# W602X.net
KiCad netlist of a schematic drawn in EAGLE
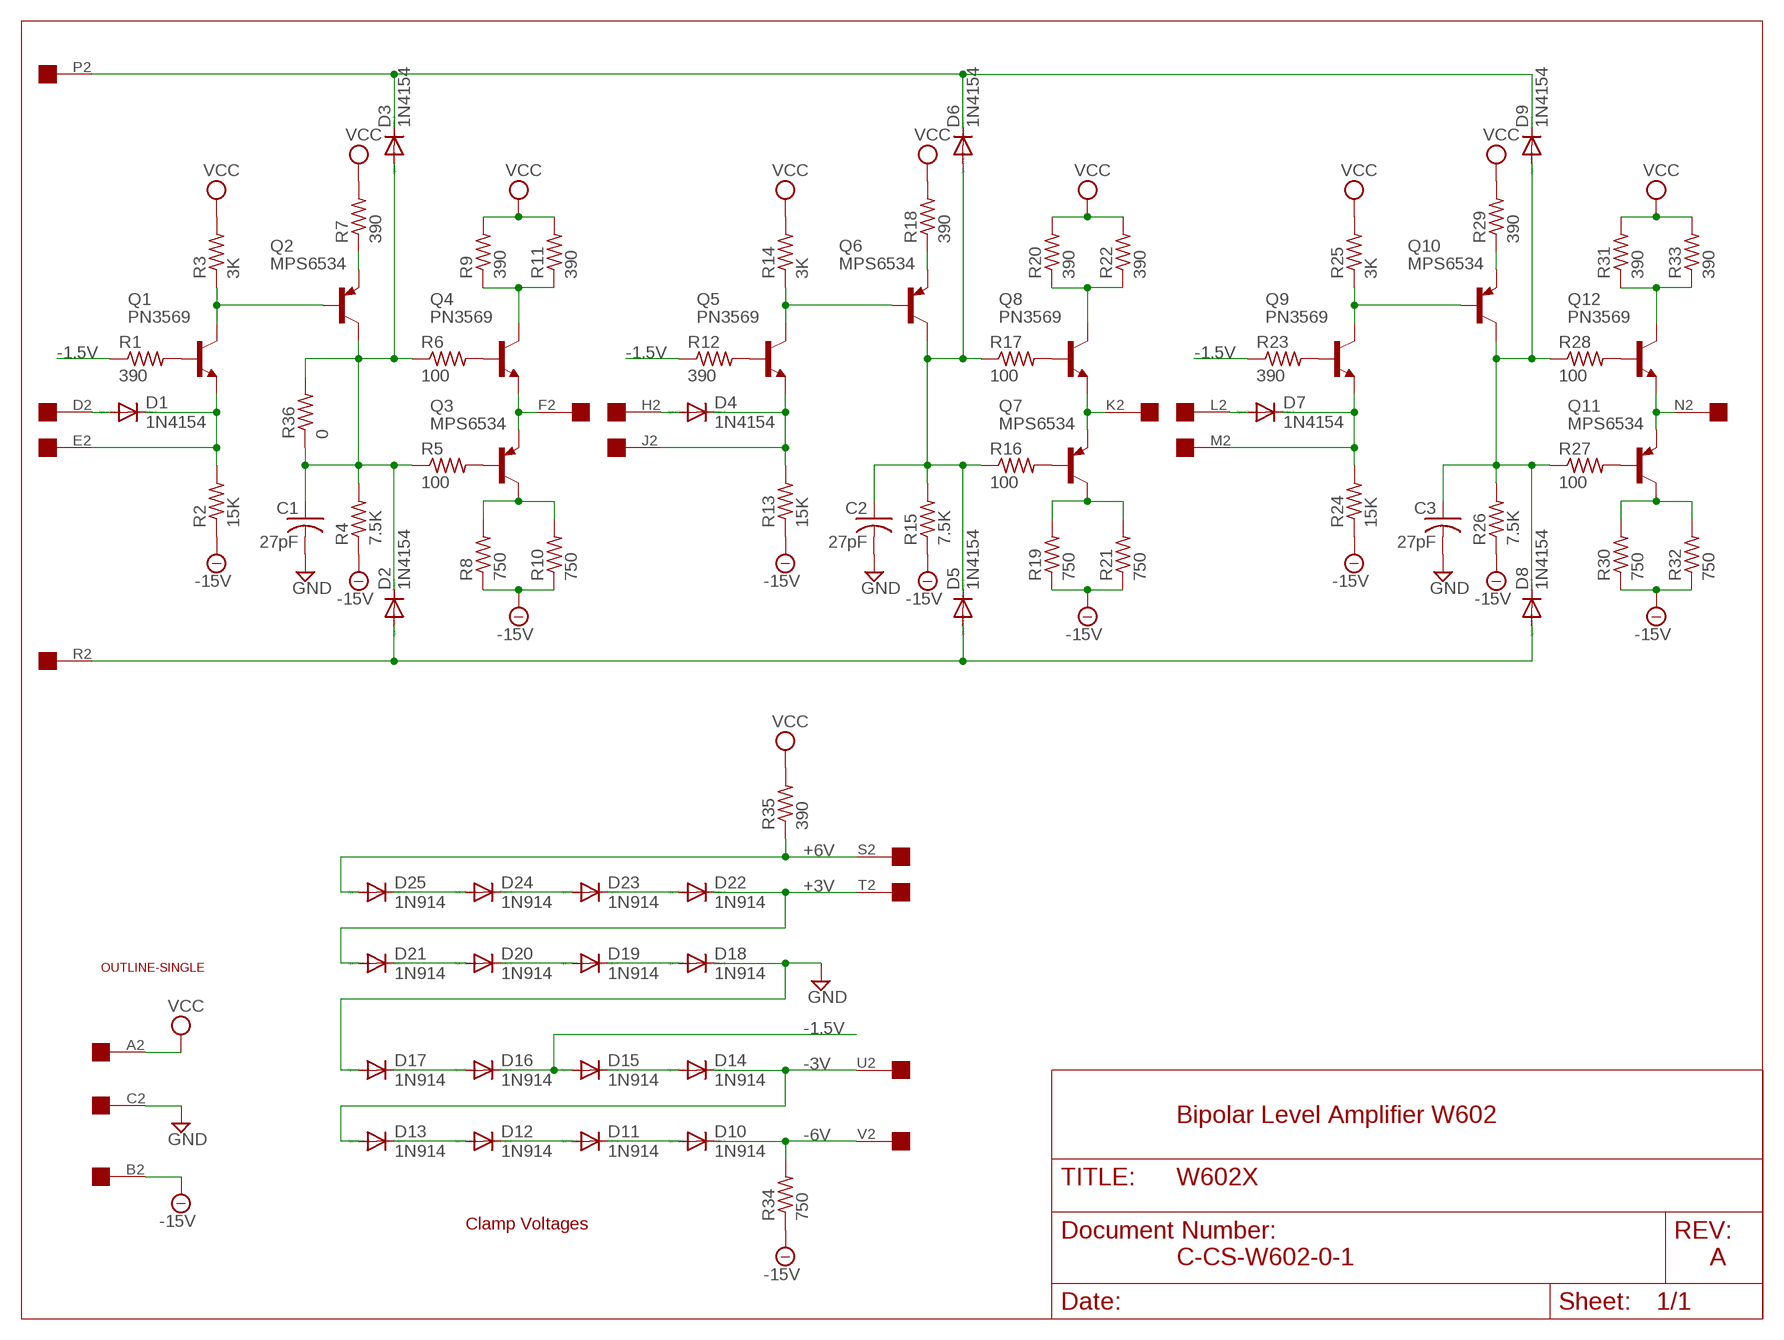
[diagram p0: schematic, sheet 1]

(export (version "E")
  (design (tool "Eeschema 10.0.6"))
  (components
    (comp (ref "C1")
      (value "27pF")
      (footprint "eagle-import:C063-025X075")
      (libsource (lib "eagle-import") (part "C-US"))
    )
    (comp (ref "C2")
      (value "27pF")
      (footprint "eagle-import:C063-025X075")
      (libsource (lib "eagle-import") (part "C-US"))
    )
    (comp (ref "C3")
      (value "27pF")
      (footprint "eagle-import:C063-025X075")
      (libsource (lib "eagle-import") (part "C-US"))
    )
    (comp (ref "D1")
      (value "1N4154")
      (footprint "eagle-import:DO35-10")
      (libsource (lib "eagle-import") (part "DIODE-DO35-10"))
    )
    (comp (ref "D2")
      (value "1N4154")
      (footprint "eagle-import:DO35-10")
      (libsource (lib "eagle-import") (part "DIODE-DO35-10"))
    )
    (comp (ref "D3")
      (value "1N4154")
      (footprint "eagle-import:DO35-10")
      (libsource (lib "eagle-import") (part "DIODE-DO35-10"))
    )
    (comp (ref "D4")
      (value "1N4154")
      (footprint "eagle-import:DO35-10")
      (libsource (lib "eagle-import") (part "DIODE-DO35-10"))
    )
    (comp (ref "D5")
      (value "1N4154")
      (footprint "eagle-import:DO35-10")
      (libsource (lib "eagle-import") (part "DIODE-DO35-10"))
    )
    (comp (ref "D6")
      (value "1N4154")
      (footprint "eagle-import:DO35-10")
      (libsource (lib "eagle-import") (part "DIODE-DO35-10"))
    )
    (comp (ref "D7")
      (value "1N4154")
      (footprint "eagle-import:DO35-10")
      (libsource (lib "eagle-import") (part "DIODE-DO35-10"))
    )
    (comp (ref "D8")
      (value "1N4154")
      (footprint "eagle-import:DO35-10")
      (libsource (lib "eagle-import") (part "DIODE-DO35-10"))
    )
    (comp (ref "D9")
      (value "1N4154")
      (footprint "eagle-import:DO35-10")
      (libsource (lib "eagle-import") (part "DIODE-DO35-10"))
    )
    (comp (ref "D10")
      (value "1N914")
      (footprint "eagle-import:DO35-10")
      (libsource (lib "eagle-import") (part "DIODE-DO35-10"))
    )
    (comp (ref "D11")
      (value "1N914")
      (footprint "eagle-import:DO35-10")
      (libsource (lib "eagle-import") (part "DIODE-DO35-10"))
    )
    (comp (ref "D12")
      (value "1N914")
      (footprint "eagle-import:DO35-10")
      (libsource (lib "eagle-import") (part "DIODE-DO35-10"))
    )
    (comp (ref "D13")
      (value "1N914")
      (footprint "eagle-import:DO35-10")
      (libsource (lib "eagle-import") (part "DIODE-DO35-10"))
    )
    (comp (ref "D14")
      (value "1N914")
      (footprint "eagle-import:DO35-10")
      (libsource (lib "eagle-import") (part "DIODE-DO35-10"))
    )
    (comp (ref "D15")
      (value "1N914")
      (footprint "eagle-import:DO35-10")
      (libsource (lib "eagle-import") (part "DIODE-DO35-10"))
    )
    (comp (ref "D16")
      (value "1N914")
      (footprint "eagle-import:DO35-10")
      (libsource (lib "eagle-import") (part "DIODE-DO35-10"))
    )
    (comp (ref "D17")
      (value "1N914")
      (footprint "eagle-import:DO35-10")
      (libsource (lib "eagle-import") (part "DIODE-DO35-10"))
    )
    (comp (ref "D18")
      (value "1N914")
      (footprint "eagle-import:DO35-10")
      (libsource (lib "eagle-import") (part "DIODE-DO35-10"))
    )
    (comp (ref "D19")
      (value "1N914")
      (footprint "eagle-import:DO35-10")
      (libsource (lib "eagle-import") (part "DIODE-DO35-10"))
    )
    (comp (ref "D20")
      (value "1N914")
      (footprint "eagle-import:DO35-10")
      (libsource (lib "eagle-import") (part "DIODE-DO35-10"))
    )
    (comp (ref "D21")
      (value "1N914")
      (footprint "eagle-import:DO35-10")
      (libsource (lib "eagle-import") (part "DIODE-DO35-10"))
    )
    (comp (ref "D22")
      (value "1N914")
      (footprint "eagle-import:DO35-10")
      (libsource (lib "eagle-import") (part "DIODE-DO35-10"))
    )
    (comp (ref "D23")
      (value "1N914")
      (footprint "eagle-import:DO35-10")
      (libsource (lib "eagle-import") (part "DIODE-DO35-10"))
    )
    (comp (ref "D24")
      (value "1N914")
      (footprint "eagle-import:DO35-10")
      (libsource (lib "eagle-import") (part "DIODE-DO35-10"))
    )
    (comp (ref "D25")
      (value "1N914")
      (footprint "eagle-import:DO35-10")
      (libsource (lib "eagle-import") (part "DIODE-DO35-10"))
    )
    (comp (ref "Q1")
      (value "PN3569")
      (footprint "eagle-import:TO5")
      (libsource (lib "eagle-import") (part "-NPN-TO5"))
    )
    (comp (ref "Q2")
      (value "MPS6534")
      (footprint "eagle-import:TO5")
      (libsource (lib "eagle-import") (part "-PNP-TO5"))
    )
    (comp (ref "Q3")
      (value "MPS6534")
      (footprint "eagle-import:TO5")
      (libsource (lib "eagle-import") (part "-PNP-TO5"))
    )
    (comp (ref "Q4")
      (value "PN3569")
      (footprint "eagle-import:TO5")
      (libsource (lib "eagle-import") (part "-NPN-TO5"))
    )
    (comp (ref "Q5")
      (value "PN3569")
      (footprint "eagle-import:TO5")
      (libsource (lib "eagle-import") (part "-NPN-TO5"))
    )
    (comp (ref "Q6")
      (value "MPS6534")
      (footprint "eagle-import:TO5")
      (libsource (lib "eagle-import") (part "-PNP-TO5"))
    )
    (comp (ref "Q7")
      (value "MPS6534")
      (footprint "eagle-import:TO5")
      (libsource (lib "eagle-import") (part "-PNP-TO5"))
    )
    (comp (ref "Q8")
      (value "PN3569")
      (footprint "eagle-import:TO5")
      (libsource (lib "eagle-import") (part "-NPN-TO5"))
    )
    (comp (ref "Q9")
      (value "PN3569")
      (footprint "eagle-import:TO5")
      (libsource (lib "eagle-import") (part "-NPN-TO5"))
    )
    (comp (ref "Q10")
      (value "MPS6534")
      (footprint "eagle-import:TO5")
      (libsource (lib "eagle-import") (part "-PNP-TO5"))
    )
    (comp (ref "Q11")
      (value "MPS6534")
      (footprint "eagle-import:TO5")
      (libsource (lib "eagle-import") (part "-PNP-TO5"))
    )
    (comp (ref "Q12")
      (value "PN3569")
      (footprint "eagle-import:TO5")
      (libsource (lib "eagle-import") (part "-NPN-TO5"))
    )
    (comp (ref "R1")
      (value "390")
      (footprint "eagle-import:0207_10")
      (libsource (lib "eagle-import") (part "R-US_0207/10"))
    )
    (comp (ref "R2")
      (value "15K")
      (footprint "eagle-import:0207_10")
      (libsource (lib "eagle-import") (part "R-US_0207/10"))
    )
    (comp (ref "R3")
      (value "3K")
      (footprint "eagle-import:0207_10")
      (libsource (lib "eagle-import") (part "R-US_0207/10"))
    )
    (comp (ref "R4")
      (value "7.5K")
      (footprint "eagle-import:0207_10")
      (libsource (lib "eagle-import") (part "R-US_0207/10"))
    )
    (comp (ref "R5")
      (value "100")
      (footprint "eagle-import:0207_10")
      (libsource (lib "eagle-import") (part "R-US_0207/10"))
    )
    (comp (ref "R6")
      (value "100")
      (footprint "eagle-import:0207_10")
      (libsource (lib "eagle-import") (part "R-US_0207/10"))
    )
    (comp (ref "R7")
      (value "390")
      (footprint "eagle-import:0207_10")
      (libsource (lib "eagle-import") (part "R-US_0207/10"))
    )
    (comp (ref "R8")
      (value "750")
      (footprint "eagle-import:0207_10")
      (libsource (lib "eagle-import") (part "R-US_0207/10"))
    )
    (comp (ref "R9")
      (value "390")
      (footprint "eagle-import:0207_10")
      (libsource (lib "eagle-import") (part "R-US_0207/10"))
    )
    (comp (ref "R10")
      (value "750")
      (footprint "eagle-import:0207_10")
      (libsource (lib "eagle-import") (part "R-US_0207/10"))
    )
    (comp (ref "R11")
      (value "390")
      (footprint "eagle-import:0207_10")
      (libsource (lib "eagle-import") (part "R-US_0207/10"))
    )
    (comp (ref "R12")
      (value "390")
      (footprint "eagle-import:0207_10")
      (libsource (lib "eagle-import") (part "R-US_0207/10"))
    )
    (comp (ref "R13")
      (value "15K")
      (footprint "eagle-import:0207_10")
      (libsource (lib "eagle-import") (part "R-US_0207/10"))
    )
    (comp (ref "R14")
      (value "3K")
      (footprint "eagle-import:0207_10")
      (libsource (lib "eagle-import") (part "R-US_0207/10"))
    )
    (comp (ref "R15")
      (value "7.5K")
      (footprint "eagle-import:0207_10")
      (libsource (lib "eagle-import") (part "R-US_0207/10"))
    )
    (comp (ref "R16")
      (value "100")
      (footprint "eagle-import:0207_10")
      (libsource (lib "eagle-import") (part "R-US_0207/10"))
    )
    (comp (ref "R17")
      (value "100")
      (footprint "eagle-import:0207_10")
      (libsource (lib "eagle-import") (part "R-US_0207/10"))
    )
    (comp (ref "R18")
      (value "390")
      (footprint "eagle-import:0207_10")
      (libsource (lib "eagle-import") (part "R-US_0207/10"))
    )
    (comp (ref "R19")
      (value "750")
      (footprint "eagle-import:0207_10")
      (libsource (lib "eagle-import") (part "R-US_0207/10"))
    )
    (comp (ref "R20")
      (value "390")
      (footprint "eagle-import:0207_10")
      (libsource (lib "eagle-import") (part "R-US_0207/10"))
    )
    (comp (ref "R21")
      (value "750")
      (footprint "eagle-import:0207_10")
      (libsource (lib "eagle-import") (part "R-US_0207/10"))
    )
    (comp (ref "R22")
      (value "390")
      (footprint "eagle-import:0207_10")
      (libsource (lib "eagle-import") (part "R-US_0207/10"))
    )
    (comp (ref "R23")
      (value "390")
      (footprint "eagle-import:0207_10")
      (libsource (lib "eagle-import") (part "R-US_0207/10"))
    )
    (comp (ref "R24")
      (value "15K")
      (footprint "eagle-import:0207_10")
      (libsource (lib "eagle-import") (part "R-US_0207/10"))
    )
    (comp (ref "R25")
      (value "3K")
      (footprint "eagle-import:0207_10")
      (libsource (lib "eagle-import") (part "R-US_0207/10"))
    )
    (comp (ref "R26")
      (value "7.5K")
      (footprint "eagle-import:0207_10")
      (libsource (lib "eagle-import") (part "R-US_0207/10"))
    )
    (comp (ref "R27")
      (value "100")
      (footprint "eagle-import:0207_10")
      (libsource (lib "eagle-import") (part "R-US_0207/10"))
    )
    (comp (ref "R28")
      (value "100")
      (footprint "eagle-import:0207_10")
      (libsource (lib "eagle-import") (part "R-US_0207/10"))
    )
    (comp (ref "R29")
      (value "390")
      (footprint "eagle-import:0207_10")
      (libsource (lib "eagle-import") (part "R-US_0207/10"))
    )
    (comp (ref "R30")
      (value "750")
      (footprint "eagle-import:0207_10")
      (libsource (lib "eagle-import") (part "R-US_0207/10"))
    )
    (comp (ref "R31")
      (value "390")
      (footprint "eagle-import:0207_10")
      (libsource (lib "eagle-import") (part "R-US_0207/10"))
    )
    (comp (ref "R32")
      (value "750")
      (footprint "eagle-import:0207_10")
      (libsource (lib "eagle-import") (part "R-US_0207/10"))
    )
    (comp (ref "R33")
      (value "390")
      (footprint "eagle-import:0207_10")
      (libsource (lib "eagle-import") (part "R-US_0207/10"))
    )
    (comp (ref "R34")
      (value "750")
      (footprint "eagle-import:0207_10")
      (libsource (lib "eagle-import") (part "R-US_0207/10"))
    )
    (comp (ref "R35")
      (value "390")
      (footprint "eagle-import:0207_10")
      (libsource (lib "eagle-import") (part "R-US_0207/10"))
    )
    (comp (ref "R36")
      (value "0")
      (footprint "eagle-import:0207_10")
      (libsource (lib "eagle-import") (part "R-US_0207/10"))
    )
    (comp (ref "U$1")
      (value "OUTLINE-SINGLE")
      (footprint "eagle-import:SINGLE")
      (libsource (lib "eagle-import") (part "OUTLINE-SINGLE"))
    )
    (comp (ref "U$2")
      (value "EDGE-1")
      (footprint "eagle-import:EDGE-CON1")
      (libsource (lib "eagle-import") (part "EDGE-1"))
    )
  )
  (nets
    (net (code "1") (name "-15V") (class "Default")
      (node (ref "R10") (pin "1") (pinfunction "1_1") (pintype "passive"))
      (node (ref "R13") (pin "1") (pinfunction "1_1") (pintype "passive"))
      (node (ref "R15") (pin "1") (pinfunction "1_1") (pintype "passive"))
      (node (ref "R19") (pin "1") (pinfunction "1_1") (pintype "passive"))
      (node (ref "R2") (pin "1") (pinfunction "1_1") (pintype "passive"))
      (node (ref "R21") (pin "1") (pinfunction "1_1") (pintype "passive"))
      (node (ref "R24") (pin "1") (pinfunction "1_1") (pintype "passive"))
      (node (ref "R26") (pin "1") (pinfunction "1_1") (pintype "passive"))
      (node (ref "R30") (pin "1") (pinfunction "1_1") (pintype "passive"))
      (node (ref "R32") (pin "1") (pinfunction "1_1") (pintype "passive"))
      (node (ref "R34") (pin "1") (pinfunction "1_1") (pintype "passive"))
      (node (ref "R4") (pin "1") (pinfunction "1_1") (pintype "passive"))
      (node (ref "R8") (pin "1") (pinfunction "1_1") (pintype "passive"))
      (node (ref "U$2") (pin "B2") (pinfunction "1_B2") (pintype "bidirectional"))
    )
    (net (code "2") (name "/+3V") (class "Default")
      (node (ref "D21") (pin "A") (pinfunction "A_A") (pintype "passive"))
      (node (ref "D22") (pin "C") (pinfunction "C_C") (pintype "passive"))
      (node (ref "U$2") (pin "T2") (pinfunction "1_T2") (pintype "bidirectional"))
    )
    (net (code "3") (name "/+6V") (class "Default")
      (node (ref "D25") (pin "A") (pinfunction "A_A") (pintype "passive"))
      (node (ref "R35") (pin "1") (pinfunction "1_1") (pintype "passive"))
      (node (ref "U$2") (pin "S2") (pinfunction "1_S2") (pintype "bidirectional"))
    )
    (net (code "4") (name "/-1.5V") (class "Default")
      (node (ref "D15") (pin "A") (pinfunction "A_A") (pintype "passive"))
      (node (ref "D16") (pin "C") (pinfunction "C_C") (pintype "passive"))
      (node (ref "R1") (pin "1") (pinfunction "1_1") (pintype "passive"))
      (node (ref "R12") (pin "1") (pinfunction "1_1") (pintype "passive"))
      (node (ref "R23") (pin "1") (pinfunction "1_1") (pintype "passive"))
    )
    (net (code "5") (name "/-3V") (class "Default")
      (node (ref "D13") (pin "A") (pinfunction "A_A") (pintype "passive"))
      (node (ref "D14") (pin "C") (pinfunction "C_C") (pintype "passive"))
      (node (ref "U$2") (pin "U2") (pinfunction "1_U2") (pintype "bidirectional"))
    )
    (net (code "6") (name "/-6V") (class "Default")
      (node (ref "D10") (pin "C") (pinfunction "C_C") (pintype "passive"))
      (node (ref "R34") (pin "2") (pinfunction "2_2") (pintype "passive"))
      (node (ref "U$2") (pin "V2") (pinfunction "1_V2") (pintype "bidirectional"))
    )
    (net (code "7") (name "GND") (class "Default")
      (node (ref "C1") (pin "2") (pinfunction "2_2") (pintype "passive"))
      (node (ref "C2") (pin "2") (pinfunction "2_2") (pintype "passive"))
      (node (ref "C3") (pin "2") (pinfunction "2_2") (pintype "passive"))
      (node (ref "D17") (pin "A") (pinfunction "A_A") (pintype "passive"))
      (node (ref "D18") (pin "C") (pinfunction "C_C") (pintype "passive"))
      (node (ref "U$2") (pin "C2") (pinfunction "1_C2") (pintype "bidirectional"))
    )
    (net (code "8") (name "Net-(D10-PadA)") (class "Default")
      (node (ref "D10") (pin "A") (pinfunction "A_A") (pintype "passive"))
      (node (ref "D11") (pin "C") (pinfunction "C_C") (pintype "passive"))
    )
    (net (code "9") (name "Net-(D11-PadA)") (class "Default")
      (node (ref "D11") (pin "A") (pinfunction "A_A") (pintype "passive"))
      (node (ref "D12") (pin "C") (pinfunction "C_C") (pintype "passive"))
    )
    (net (code "10") (name "Net-(D12-PadA)") (class "Default")
      (node (ref "D12") (pin "A") (pinfunction "A_A") (pintype "passive"))
      (node (ref "D13") (pin "C") (pinfunction "C_C") (pintype "passive"))
    )
    (net (code "11") (name "Net-(D14-PadA)") (class "Default")
      (node (ref "D14") (pin "A") (pinfunction "A_A") (pintype "passive"))
      (node (ref "D15") (pin "C") (pinfunction "C_C") (pintype "passive"))
    )
    (net (code "12") (name "Net-(D16-PadA)") (class "Default")
      (node (ref "D16") (pin "A") (pinfunction "A_A") (pintype "passive"))
      (node (ref "D17") (pin "C") (pinfunction "C_C") (pintype "passive"))
    )
    (net (code "13") (name "Net-(D18-PadA)") (class "Default")
      (node (ref "D18") (pin "A") (pinfunction "A_A") (pintype "passive"))
      (node (ref "D19") (pin "C") (pinfunction "C_C") (pintype "passive"))
    )
    (net (code "14") (name "Net-(D19-PadA)") (class "Default")
      (node (ref "D19") (pin "A") (pinfunction "A_A") (pintype "passive"))
      (node (ref "D20") (pin "C") (pinfunction "C_C") (pintype "passive"))
    )
    (net (code "15") (name "Net-(D20-PadA)") (class "Default")
      (node (ref "D20") (pin "A") (pinfunction "A_A") (pintype "passive"))
      (node (ref "D21") (pin "C") (pinfunction "C_C") (pintype "passive"))
    )
    (net (code "16") (name "Net-(D22-PadA)") (class "Default")
      (node (ref "D22") (pin "A") (pinfunction "A_A") (pintype "passive"))
      (node (ref "D23") (pin "C") (pinfunction "C_C") (pintype "passive"))
    )
    (net (code "17") (name "Net-(D23-PadA)") (class "Default")
      (node (ref "D23") (pin "A") (pinfunction "A_A") (pintype "passive"))
      (node (ref "D24") (pin "C") (pinfunction "C_C") (pintype "passive"))
    )
    (net (code "18") (name "Net-(D24-PadA)") (class "Default")
      (node (ref "D24") (pin "A") (pinfunction "A_A") (pintype "passive"))
      (node (ref "D25") (pin "C") (pinfunction "C_C") (pintype "passive"))
    )
    (net (code "19") (name "Net-(Q1-B)") (class "Default")
      (node (ref "Q1") (pin "2") (pinfunction "B_2") (pintype "passive"))
      (node (ref "R1") (pin "2") (pinfunction "2_2") (pintype "passive"))
    )
    (net (code "20") (name "Net-(Q1-C)") (class "Default")
      (node (ref "Q1") (pin "3") (pinfunction "C_3") (pintype "passive"))
      (node (ref "Q2") (pin "2") (pinfunction "B_2") (pintype "passive"))
      (node (ref "R3") (pin "1") (pinfunction "1_1") (pintype "passive"))
    )
    (net (code "21") (name "Net-(Q1-E)") (class "Default")
      (node (ref "D1") (pin "C") (pinfunction "C_C") (pintype "passive"))
      (node (ref "Q1") (pin "1") (pinfunction "E_1") (pintype "passive"))
      (node (ref "R2") (pin "2") (pinfunction "2_2") (pintype "passive"))
      (node (ref "U$2") (pin "E2") (pinfunction "1_E2") (pintype "bidirectional"))
    )
    (net (code "22") (name "Net-(Q2-C)") (class "Default")
      (node (ref "C1") (pin "1") (pinfunction "1_1") (pintype "passive"))
      (node (ref "D2") (pin "C") (pinfunction "C_C") (pintype "passive"))
      (node (ref "D3") (pin "A") (pinfunction "A_A") (pintype "passive"))
      (node (ref "Q2") (pin "3") (pinfunction "C_3") (pintype "passive"))
      (node (ref "R36") (pin "1") (pinfunction "1_1") (pintype "passive"))
      (node (ref "R36") (pin "2") (pinfunction "2_2") (pintype "passive"))
      (node (ref "R4") (pin "2") (pinfunction "2_2") (pintype "passive"))
      (node (ref "R5") (pin "1") (pinfunction "1_1") (pintype "passive"))
      (node (ref "R6") (pin "1") (pinfunction "1_1") (pintype "passive"))
    )
    (net (code "23") (name "Net-(Q2-E)") (class "Default")
      (node (ref "Q2") (pin "1") (pinfunction "E_1") (pintype "passive"))
      (node (ref "R7") (pin "1") (pinfunction "1_1") (pintype "passive"))
    )
    (net (code "24") (name "Net-(Q3-B)") (class "Default")
      (node (ref "Q3") (pin "2") (pinfunction "B_2") (pintype "passive"))
      (node (ref "R5") (pin "2") (pinfunction "2_2") (pintype "passive"))
    )
    (net (code "25") (name "Net-(Q3-C)") (class "Default")
      (node (ref "Q3") (pin "3") (pinfunction "C_3") (pintype "passive"))
      (node (ref "R10") (pin "2") (pinfunction "2_2") (pintype "passive"))
      (node (ref "R8") (pin "2") (pinfunction "2_2") (pintype "passive"))
    )
    (net (code "26") (name "Net-(Q3-E)") (class "Default")
      (node (ref "Q3") (pin "1") (pinfunction "E_1") (pintype "passive"))
      (node (ref "Q4") (pin "1") (pinfunction "E_1") (pintype "passive"))
      (node (ref "U$2") (pin "F2") (pinfunction "1_F2") (pintype "bidirectional"))
    )
    (net (code "27") (name "Net-(Q4-B)") (class "Default")
      (node (ref "Q4") (pin "2") (pinfunction "B_2") (pintype "passive"))
      (node (ref "R6") (pin "2") (pinfunction "2_2") (pintype "passive"))
    )
    (net (code "28") (name "Net-(Q4-C)") (class "Default")
      (node (ref "Q4") (pin "3") (pinfunction "C_3") (pintype "passive"))
      (node (ref "R11") (pin "1") (pinfunction "1_1") (pintype "passive"))
      (node (ref "R9") (pin "1") (pinfunction "1_1") (pintype "passive"))
    )
    (net (code "29") (name "Net-(Q5-B)") (class "Default")
      (node (ref "Q5") (pin "2") (pinfunction "B_2") (pintype "passive"))
      (node (ref "R12") (pin "2") (pinfunction "2_2") (pintype "passive"))
    )
    (net (code "30") (name "Net-(Q5-C)") (class "Default")
      (node (ref "Q5") (pin "3") (pinfunction "C_3") (pintype "passive"))
      (node (ref "Q6") (pin "2") (pinfunction "B_2") (pintype "passive"))
      (node (ref "R14") (pin "1") (pinfunction "1_1") (pintype "passive"))
    )
    (net (code "31") (name "Net-(Q5-E)") (class "Default")
      (node (ref "D4") (pin "C") (pinfunction "C_C") (pintype "passive"))
      (node (ref "Q5") (pin "1") (pinfunction "E_1") (pintype "passive"))
      (node (ref "R13") (pin "2") (pinfunction "2_2") (pintype "passive"))
      (node (ref "U$2") (pin "J2") (pinfunction "1_J2") (pintype "bidirectional"))
    )
    (net (code "32") (name "Net-(Q6-C)") (class "Default")
      (node (ref "C2") (pin "1") (pinfunction "1_1") (pintype "passive"))
      (node (ref "D5") (pin "C") (pinfunction "C_C") (pintype "passive"))
      (node (ref "D6") (pin "A") (pinfunction "A_A") (pintype "passive"))
      (node (ref "Q6") (pin "3") (pinfunction "C_3") (pintype "passive"))
      (node (ref "R15") (pin "2") (pinfunction "2_2") (pintype "passive"))
      (node (ref "R16") (pin "1") (pinfunction "1_1") (pintype "passive"))
      (node (ref "R17") (pin "1") (pinfunction "1_1") (pintype "passive"))
    )
    (net (code "33") (name "Net-(Q6-E)") (class "Default")
      (node (ref "Q6") (pin "1") (pinfunction "E_1") (pintype "passive"))
      (node (ref "R18") (pin "1") (pinfunction "1_1") (pintype "passive"))
    )
    (net (code "34") (name "Net-(Q7-B)") (class "Default")
      (node (ref "Q7") (pin "2") (pinfunction "B_2") (pintype "passive"))
      (node (ref "R16") (pin "2") (pinfunction "2_2") (pintype "passive"))
    )
    (net (code "35") (name "Net-(Q7-C)") (class "Default")
      (node (ref "Q7") (pin "3") (pinfunction "C_3") (pintype "passive"))
      (node (ref "R19") (pin "2") (pinfunction "2_2") (pintype "passive"))
      (node (ref "R21") (pin "2") (pinfunction "2_2") (pintype "passive"))
    )
    (net (code "36") (name "Net-(Q7-E)") (class "Default")
      (node (ref "Q7") (pin "1") (pinfunction "E_1") (pintype "passive"))
      (node (ref "Q8") (pin "1") (pinfunction "E_1") (pintype "passive"))
      (node (ref "U$2") (pin "K2") (pinfunction "1_K2") (pintype "bidirectional"))
    )
    (net (code "37") (name "Net-(Q8-B)") (class "Default")
      (node (ref "Q8") (pin "2") (pinfunction "B_2") (pintype "passive"))
      (node (ref "R17") (pin "2") (pinfunction "2_2") (pintype "passive"))
    )
    (net (code "38") (name "Net-(Q8-C)") (class "Default")
      (node (ref "Q8") (pin "3") (pinfunction "C_3") (pintype "passive"))
      (node (ref "R20") (pin "1") (pinfunction "1_1") (pintype "passive"))
      (node (ref "R22") (pin "1") (pinfunction "1_1") (pintype "passive"))
    )
    (net (code "39") (name "Net-(Q9-B)") (class "Default")
      (node (ref "Q9") (pin "2") (pinfunction "B_2") (pintype "passive"))
      (node (ref "R23") (pin "2") (pinfunction "2_2") (pintype "passive"))
    )
    (net (code "40") (name "Net-(Q9-E)") (class "Default")
      (node (ref "D7") (pin "C") (pinfunction "C_C") (pintype "passive"))
      (node (ref "Q9") (pin "1") (pinfunction "E_1") (pintype "passive"))
      (node (ref "R24") (pin "2") (pinfunction "2_2") (pintype "passive"))
      (node (ref "U$2") (pin "M2") (pinfunction "1_M2") (pintype "bidirectional"))
    )
    (net (code "41") (name "Net-(Q10-B)") (class "Default")
      (node (ref "Q10") (pin "2") (pinfunction "B_2") (pintype "passive"))
      (node (ref "Q9") (pin "3") (pinfunction "C_3") (pintype "passive"))
      (node (ref "R25") (pin "1") (pinfunction "1_1") (pintype "passive"))
    )
    (net (code "42") (name "Net-(Q10-C)") (class "Default")
      (node (ref "C3") (pin "1") (pinfunction "1_1") (pintype "passive"))
      (node (ref "D8") (pin "C") (pinfunction "C_C") (pintype "passive"))
      (node (ref "D9") (pin "A") (pinfunction "A_A") (pintype "passive"))
      (node (ref "Q10") (pin "3") (pinfunction "C_3") (pintype "passive"))
      (node (ref "R26") (pin "2") (pinfunction "2_2") (pintype "passive"))
      (node (ref "R27") (pin "1") (pinfunction "1_1") (pintype "passive"))
      (node (ref "R28") (pin "1") (pinfunction "1_1") (pintype "passive"))
    )
    (net (code "43") (name "Net-(Q10-E)") (class "Default")
      (node (ref "Q10") (pin "1") (pinfunction "E_1") (pintype "passive"))
      (node (ref "R29") (pin "1") (pinfunction "1_1") (pintype "passive"))
    )
    (net (code "44") (name "Net-(Q11-B)") (class "Default")
      (node (ref "Q11") (pin "2") (pinfunction "B_2") (pintype "passive"))
      (node (ref "R27") (pin "2") (pinfunction "2_2") (pintype "passive"))
    )
    (net (code "45") (name "Net-(Q11-C)") (class "Default")
      (node (ref "Q11") (pin "3") (pinfunction "C_3") (pintype "passive"))
      (node (ref "R30") (pin "2") (pinfunction "2_2") (pintype "passive"))
      (node (ref "R32") (pin "2") (pinfunction "2_2") (pintype "passive"))
    )
    (net (code "46") (name "Net-(Q11-E)") (class "Default")
      (node (ref "Q11") (pin "1") (pinfunction "E_1") (pintype "passive"))
      (node (ref "Q12") (pin "1") (pinfunction "E_1") (pintype "passive"))
      (node (ref "U$2") (pin "N2") (pinfunction "1_N2") (pintype "bidirectional"))
    )
    (net (code "47") (name "Net-(Q12-B)") (class "Default")
      (node (ref "Q12") (pin "2") (pinfunction "B_2") (pintype "passive"))
      (node (ref "R28") (pin "2") (pinfunction "2_2") (pintype "passive"))
    )
    (net (code "48") (name "Net-(Q12-C)") (class "Default")
      (node (ref "Q12") (pin "3") (pinfunction "C_3") (pintype "passive"))
      (node (ref "R31") (pin "1") (pinfunction "1_1") (pintype "passive"))
      (node (ref "R33") (pin "1") (pinfunction "1_1") (pintype "passive"))
    )
    (net (code "49") (name "Net-(U$2D-1)") (class "Default")
      (node (ref "D1") (pin "A") (pinfunction "A_A") (pintype "passive"))
      (node (ref "U$2") (pin "D2") (pinfunction "1_D2") (pintype "bidirectional"))
    )
    (net (code "50") (name "Net-(U$2G-1)") (class "Default")
      (node (ref "D4") (pin "A") (pinfunction "A_A") (pintype "passive"))
      (node (ref "U$2") (pin "H2") (pinfunction "1_H2") (pintype "bidirectional"))
    )
    (net (code "51") (name "Net-(U$2J-1)") (class "Default")
      (node (ref "D7") (pin "A") (pinfunction "A_A") (pintype "passive"))
      (node (ref "U$2") (pin "L2") (pinfunction "1_L2") (pintype "bidirectional"))
    )
    (net (code "52") (name "Net-(U$2M-1)") (class "Default")
      (node (ref "D3") (pin "C") (pinfunction "C_C") (pintype "passive"))
      (node (ref "D6") (pin "C") (pinfunction "C_C") (pintype "passive"))
      (node (ref "D9") (pin "C") (pinfunction "C_C") (pintype "passive"))
      (node (ref "U$2") (pin "P2") (pinfunction "1_P2") (pintype "bidirectional"))
    )
    (net (code "53") (name "Net-(U$2N-1)") (class "Default")
      (node (ref "D2") (pin "A") (pinfunction "A_A") (pintype "passive"))
      (node (ref "D5") (pin "A") (pinfunction "A_A") (pintype "passive"))
      (node (ref "D8") (pin "A") (pinfunction "A_A") (pintype "passive"))
      (node (ref "U$2") (pin "R2") (pinfunction "1_R2") (pintype "bidirectional"))
    )
    (net (code "54") (name "VCC") (class "Default")
      (node (ref "R11") (pin "2") (pinfunction "2_2") (pintype "passive"))
      (node (ref "R14") (pin "2") (pinfunction "2_2") (pintype "passive"))
      (node (ref "R18") (pin "2") (pinfunction "2_2") (pintype "passive"))
      (node (ref "R20") (pin "2") (pinfunction "2_2") (pintype "passive"))
      (node (ref "R22") (pin "2") (pinfunction "2_2") (pintype "passive"))
      (node (ref "R25") (pin "2") (pinfunction "2_2") (pintype "passive"))
      (node (ref "R29") (pin "2") (pinfunction "2_2") (pintype "passive"))
      (node (ref "R3") (pin "2") (pinfunction "2_2") (pintype "passive"))
      (node (ref "R31") (pin "2") (pinfunction "2_2") (pintype "passive"))
      (node (ref "R33") (pin "2") (pinfunction "2_2") (pintype "passive"))
      (node (ref "R35") (pin "2") (pinfunction "2_2") (pintype "passive"))
      (node (ref "R7") (pin "2") (pinfunction "2_2") (pintype "passive"))
      (node (ref "R9") (pin "2") (pinfunction "2_2") (pintype "passive"))
      (node (ref "U$2") (pin "A2") (pinfunction "1_A2") (pintype "bidirectional"))
    )
  )
)
